# Conn_B.net
KiCad netlist of a schematic drawn in Altium Designer
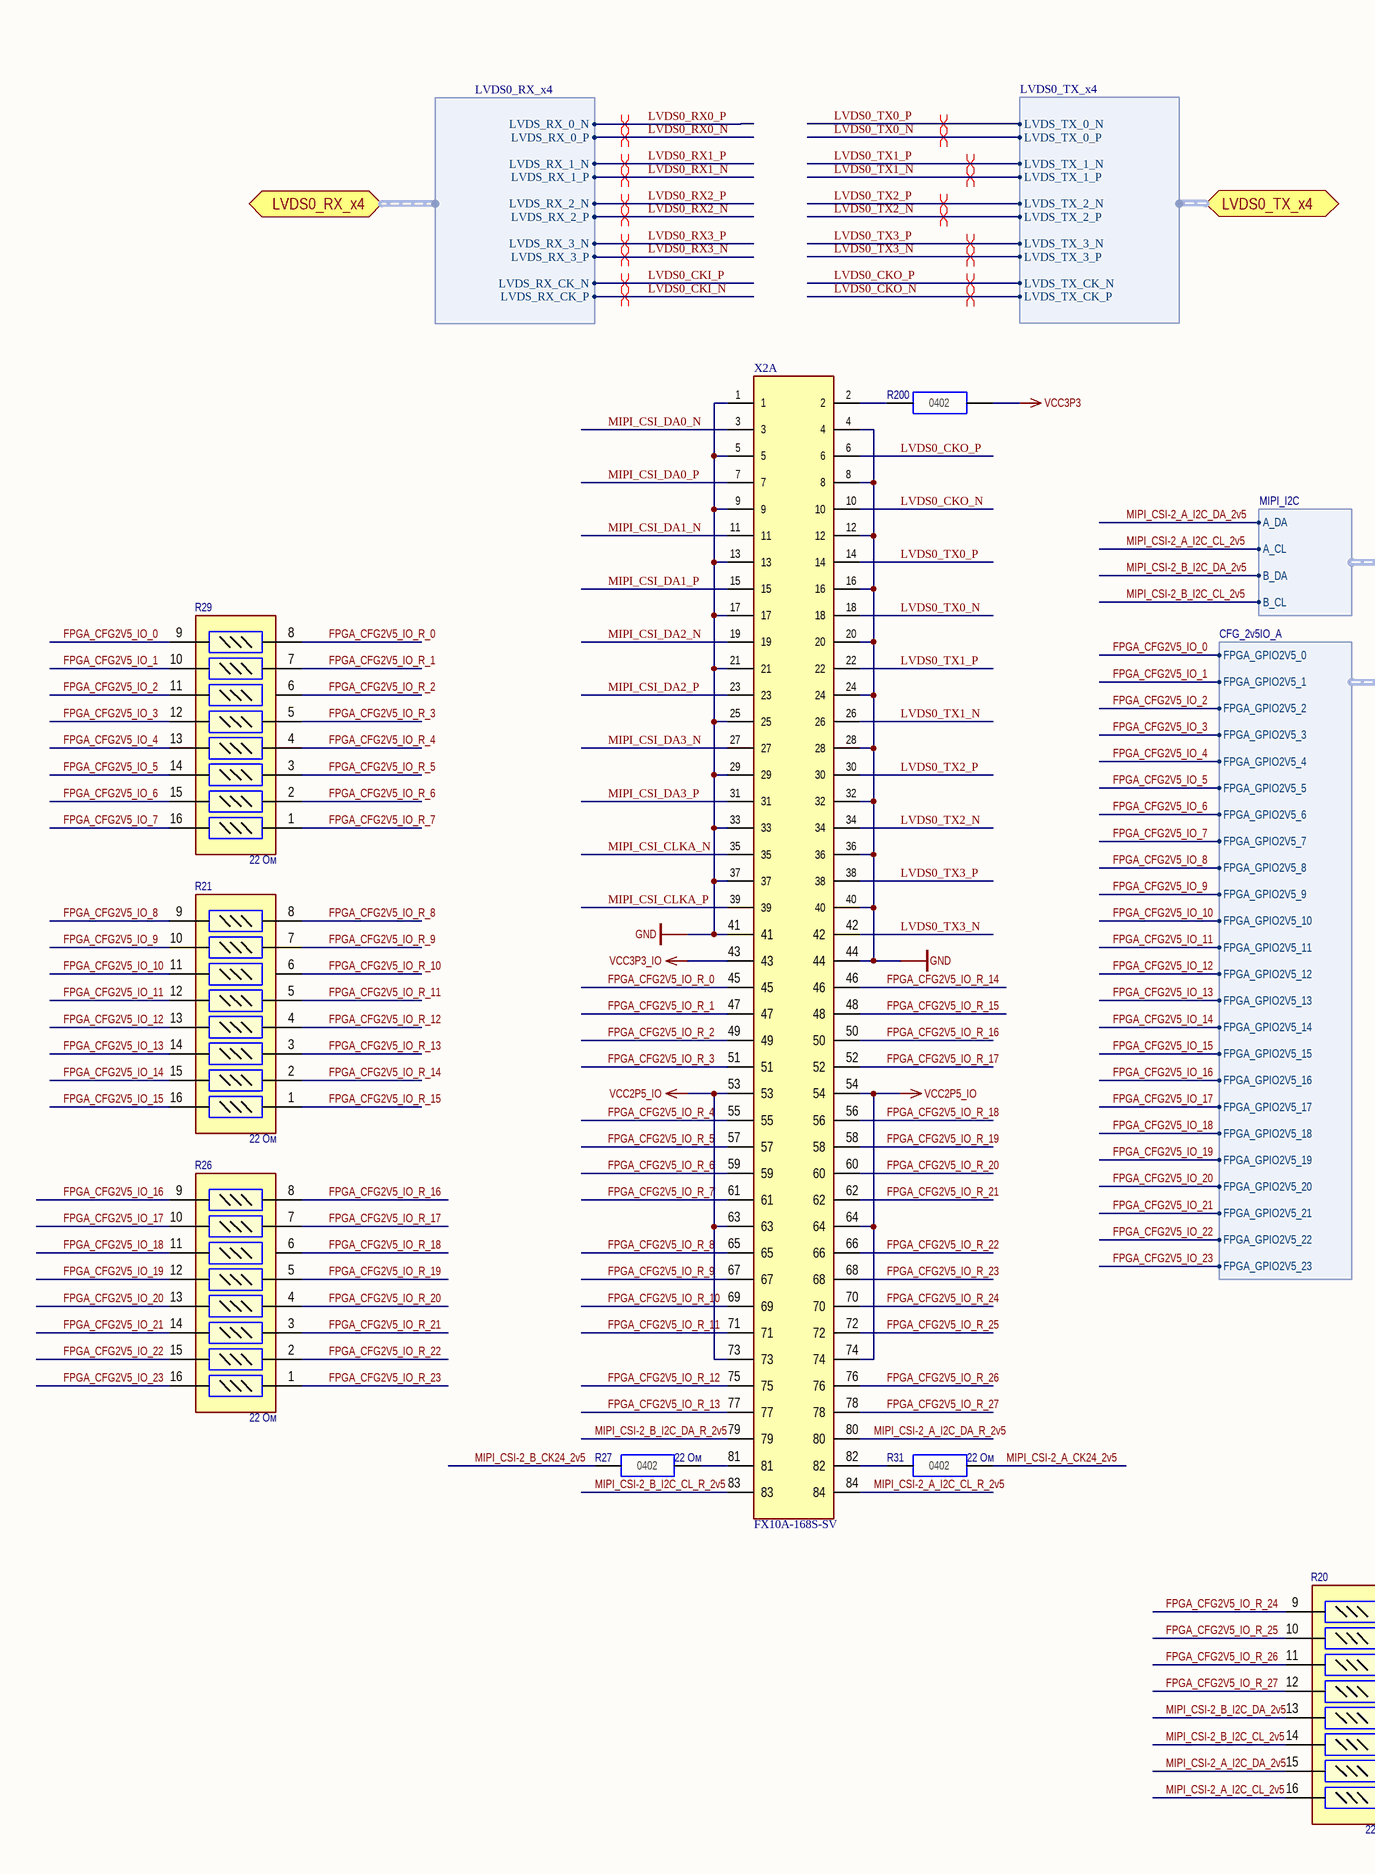
[diagram p0: Conn_B.SchDoc, left]
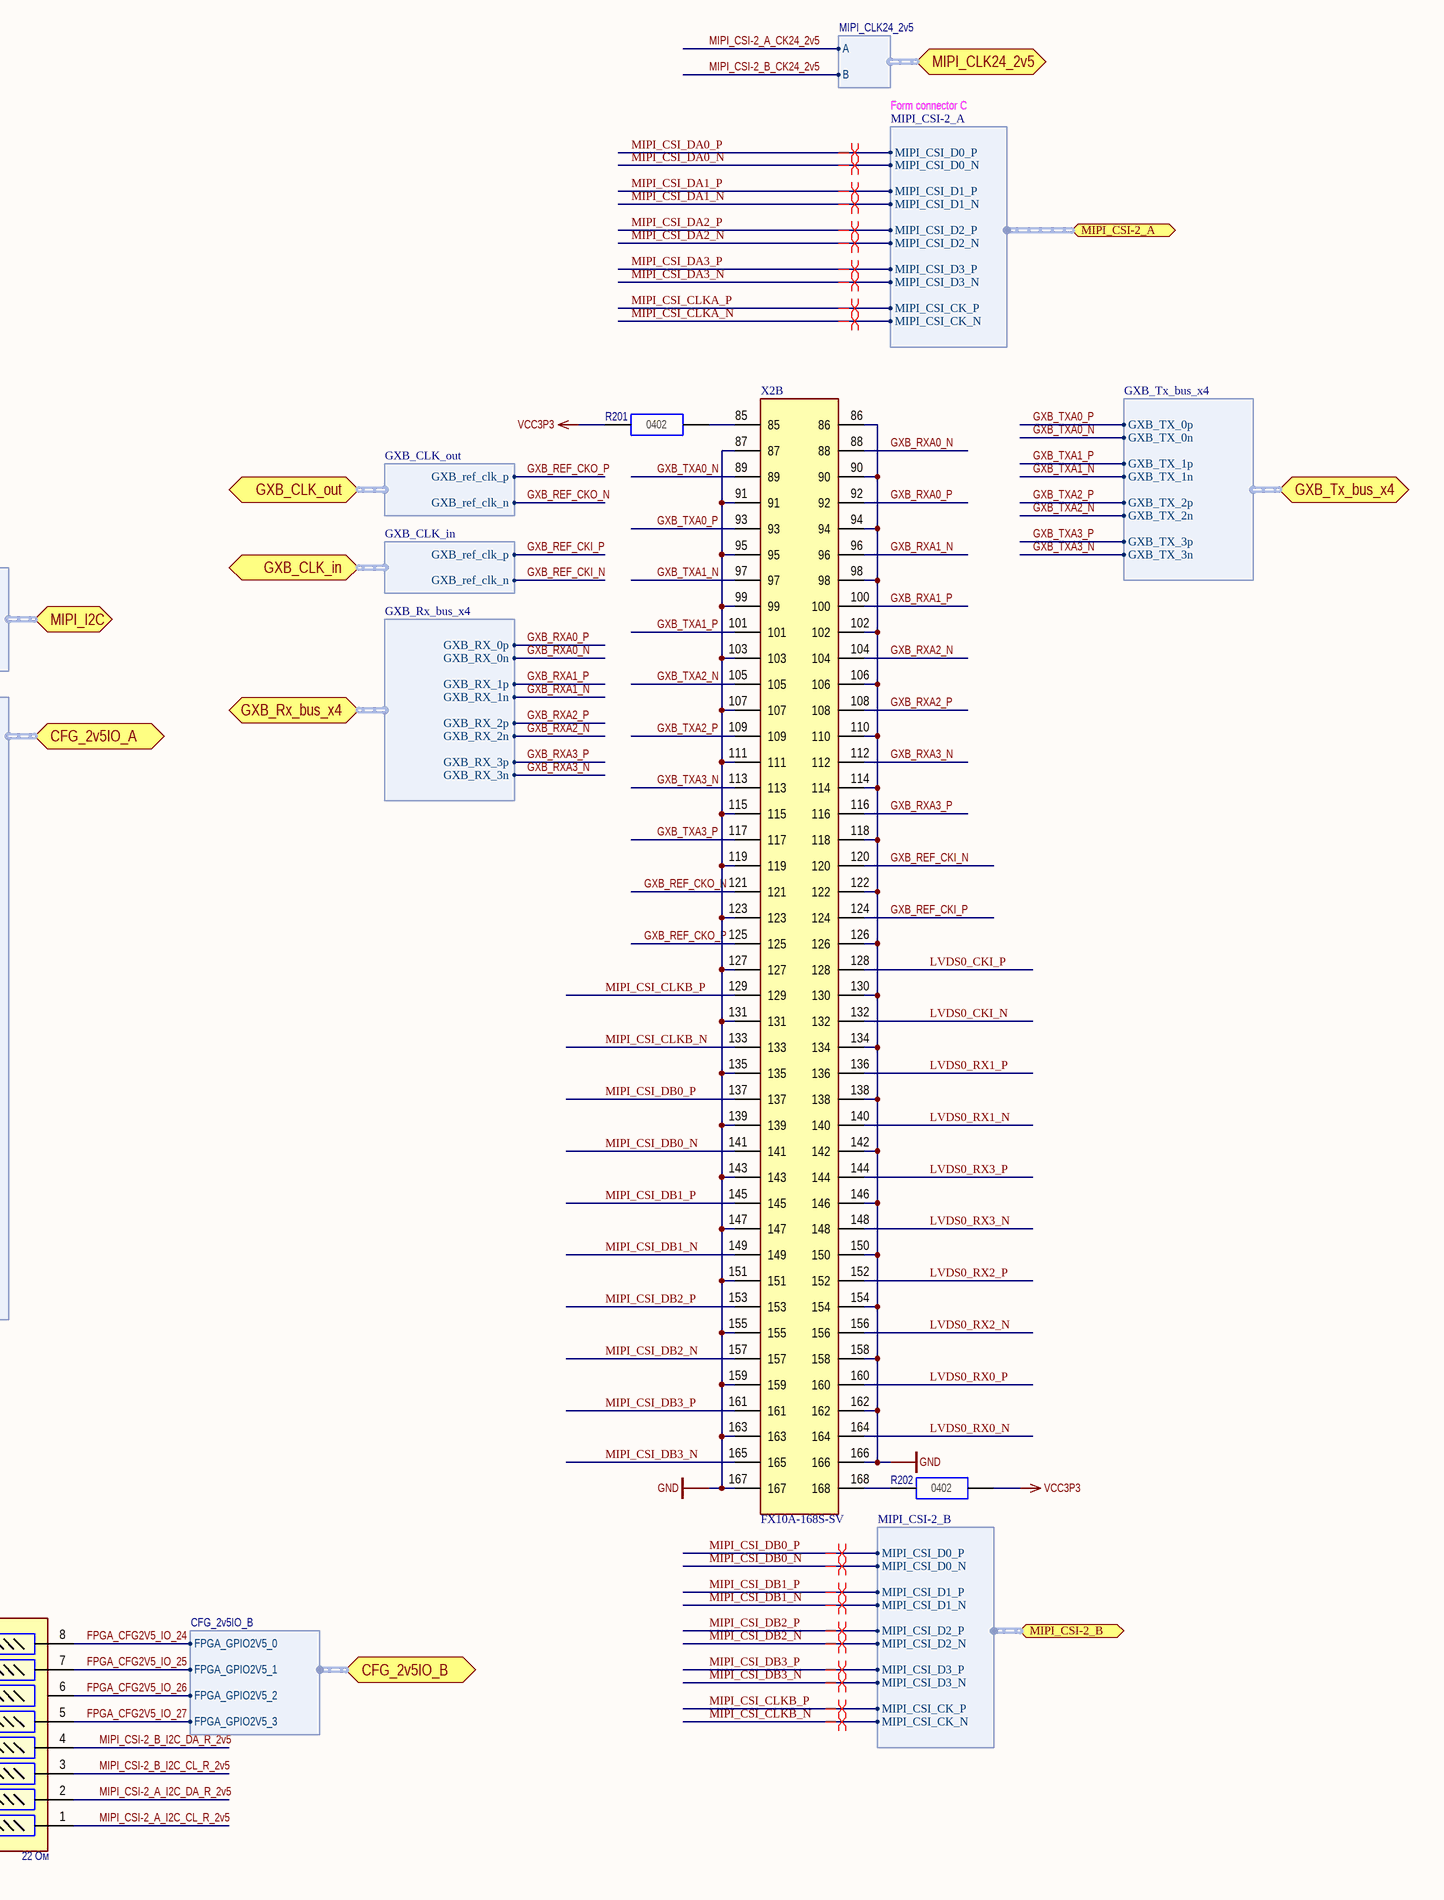
[diagram p1: Conn_B.SchDoc, right]

(export (version "E")
  (design (tool "Eeschema 10.0.6"))
  (components
    (comp (ref "R20")
      (value "22 Ом")
      (footprint "YC248")
      (description "Набор чип резисторов")
      (fields (field (name "Comment") "YC248-JR-07-22 Ом"))
      (libsource (lib "SD_IC") (part "YC248-JR-07-#"))
    )
    (comp (ref "R21")
      (value "22 Ом")
      (footprint "YC248")
      (description "Набор чип резисторов")
      (fields (field (name "Comment") "YC248-JR-07-22 Ом"))
      (libsource (lib "SD_IC") (part "YC248-JR-07-#"))
    )
    (comp (ref "R26")
      (value "22 Ом")
      (footprint "YC248")
      (description "Набор чип резисторов")
      (fields (field (name "Comment") "YC248-JR-07-22 Ом"))
      (libsource (lib "SD_IC") (part "YC248-JR-07-#"))
    )
    (comp (ref "R27")
      (value "22 Ом")
      (footprint "CR0402(1005)")
      (description "Чип резистор")
      (fields (field (name "TOLERANCE") "5%") (field (name "Comment") "CR0402-22 Ом-±5%"))
      (libsource (lib "Чип резисторы") (part "CR0402-#-±5%"))
    )
    (comp (ref "R29")
      (value "22 Ом")
      (footprint "YC248")
      (description "Набор чип резисторов")
      (fields (field (name "Comment") "YC248-JR-07-22 Ом"))
      (libsource (lib "SD_IC") (part "YC248-JR-07-#"))
    )
    (comp (ref "R31")
      (value "22 Ом")
      (footprint "CR0402(1005)")
      (description "Чип резистор")
      (fields (field (name "TOLERANCE") "5%") (field (name "Comment") "CR0402-22 Ом-±5%"))
      (libsource (lib "Чип резисторы") (part "CR0402-#-±5%"))
    )
    (comp (ref "R200")
      (value "CR0402-0 Ом-±5%")
      (footprint "CR0402(1005)")
      (description "Чип резистор")
      (fields (field (name "TOLERANCE") "5%"))
      (libsource (lib "Резисторы") (part "CR0402-#-±5%"))
    )
    (comp (ref "R201")
      (value "CR0402-0 Ом-±5%")
      (footprint "CR0402(1005)")
      (description "Чип резистор")
      (fields (field (name "TOLERANCE") "5%"))
      (libsource (lib "Резисторы") (part "CR0402-#-±5%"))
    )
    (comp (ref "R202")
      (value "CR0402-0 Ом-±5%")
      (footprint "CR0402(1005)")
      (description "Чип резистор")
      (fields (field (name "TOLERANCE") "5%"))
      (libsource (lib "Резисторы") (part "CR0402-#-±5%"))
    )
    (comp (ref "X2")
      (value "FX10A-168S-SV")
      (footprint "FX10A-168S-SV")
      (libsource (lib "SD_IC") (part "FX10A-168S-SV"))
    )
  )
  (nets
    (net (code "13") (name "/FPGA_CFG2V5_IO_0") (class "Default")
      (node (ref "R29") (pin "9") (pintype "passive"))
    )
    (net (code "14") (name "/FPGA_CFG2V5_IO_1") (class "Default")
      (node (ref "R29") (pin "10") (pintype "passive"))
    )
    (net (code "15") (name "/FPGA_CFG2V5_IO_2") (class "Default")
      (node (ref "R29") (pin "11") (pintype "passive"))
    )
    (net (code "16") (name "/FPGA_CFG2V5_IO_3") (class "Default")
      (node (ref "R29") (pin "12") (pintype "passive"))
    )
    (net (code "17") (name "/FPGA_CFG2V5_IO_4") (class "Default")
      (node (ref "R29") (pin "13") (pintype "passive"))
    )
    (net (code "18") (name "/FPGA_CFG2V5_IO_5") (class "Default")
      (node (ref "R29") (pin "14") (pintype "passive"))
    )
    (net (code "19") (name "/FPGA_CFG2V5_IO_6") (class "Default")
      (node (ref "R29") (pin "15") (pintype "passive"))
    )
    (net (code "20") (name "/FPGA_CFG2V5_IO_7") (class "Default")
      (node (ref "R29") (pin "16") (pintype "passive"))
    )
    (net (code "21") (name "/FPGA_CFG2V5_IO_8") (class "Default")
      (node (ref "R21") (pin "9") (pintype "passive"))
    )
    (net (code "22") (name "/FPGA_CFG2V5_IO_9") (class "Default")
      (node (ref "R21") (pin "10") (pintype "passive"))
    )
    (net (code "23") (name "/FPGA_CFG2V5_IO_10") (class "Default")
      (node (ref "R21") (pin "11") (pintype "passive"))
    )
    (net (code "24") (name "/FPGA_CFG2V5_IO_11") (class "Default")
      (node (ref "R21") (pin "12") (pintype "passive"))
    )
    (net (code "25") (name "/FPGA_CFG2V5_IO_12") (class "Default")
      (node (ref "R21") (pin "13") (pintype "passive"))
    )
    (net (code "26") (name "/FPGA_CFG2V5_IO_13") (class "Default")
      (node (ref "R21") (pin "14") (pintype "passive"))
    )
    (net (code "27") (name "/FPGA_CFG2V5_IO_14") (class "Default")
      (node (ref "R21") (pin "15") (pintype "passive"))
    )
    (net (code "28") (name "/FPGA_CFG2V5_IO_15") (class "Default")
      (node (ref "R21") (pin "16") (pintype "passive"))
    )
    (net (code "29") (name "/FPGA_CFG2V5_IO_16") (class "Default")
      (node (ref "R26") (pin "9") (pintype "passive"))
    )
    (net (code "30") (name "/FPGA_CFG2V5_IO_17") (class "Default")
      (node (ref "R26") (pin "10") (pintype "passive"))
    )
    (net (code "31") (name "/FPGA_CFG2V5_IO_18") (class "Default")
      (node (ref "R26") (pin "11") (pintype "passive"))
    )
    (net (code "32") (name "/FPGA_CFG2V5_IO_19") (class "Default")
      (node (ref "R26") (pin "12") (pintype "passive"))
    )
    (net (code "33") (name "/FPGA_CFG2V5_IO_20") (class "Default")
      (node (ref "R26") (pin "13") (pintype "passive"))
    )
    (net (code "34") (name "/FPGA_CFG2V5_IO_21") (class "Default")
      (node (ref "R26") (pin "14") (pintype "passive"))
    )
    (net (code "35") (name "/FPGA_CFG2V5_IO_22") (class "Default")
      (node (ref "R26") (pin "15") (pintype "passive"))
    )
    (net (code "36") (name "/FPGA_CFG2V5_IO_23") (class "Default")
      (node (ref "R26") (pin "16") (pintype "passive"))
    )
    (net (code "37") (name "/FPGA_CFG2V5_IO_24") (class "Default")
      (node (ref "R20") (pin "8") (pintype "passive"))
    )
    (net (code "38") (name "/FPGA_CFG2V5_IO_25") (class "Default")
      (node (ref "R20") (pin "7") (pintype "passive"))
    )
    (net (code "39") (name "/FPGA_CFG2V5_IO_26") (class "Default")
      (node (ref "R20") (pin "6") (pintype "passive"))
    )
    (net (code "40") (name "/FPGA_CFG2V5_IO_27") (class "Default")
      (node (ref "R20") (pin "5") (pintype "passive"))
    )
    (net (code "41") (name "/FPGA_CFG2V5_IO_R_0") (class "Default")
      (node (ref "R29") (pin "8") (pintype "passive"))
      (node (ref "X2") (pin "45") (pinfunction "45_45") (pintype "passive"))
    )
    (net (code "42") (name "/FPGA_CFG2V5_IO_R_1") (class "Default")
      (node (ref "R29") (pin "7") (pintype "passive"))
      (node (ref "X2") (pin "47") (pinfunction "47_47") (pintype "passive"))
    )
    (net (code "43") (name "/FPGA_CFG2V5_IO_R_2") (class "Default")
      (node (ref "R29") (pin "6") (pintype "passive"))
      (node (ref "X2") (pin "49") (pinfunction "49_49") (pintype "passive"))
    )
    (net (code "44") (name "/FPGA_CFG2V5_IO_R_3") (class "Default")
      (node (ref "R29") (pin "5") (pintype "passive"))
      (node (ref "X2") (pin "51") (pinfunction "51_51") (pintype "passive"))
    )
    (net (code "45") (name "/FPGA_CFG2V5_IO_R_4") (class "Default")
      (node (ref "R29") (pin "4") (pintype "passive"))
      (node (ref "X2") (pin "55") (pinfunction "55_55") (pintype "passive"))
    )
    (net (code "46") (name "/FPGA_CFG2V5_IO_R_5") (class "Default")
      (node (ref "R29") (pin "3") (pintype "passive"))
      (node (ref "X2") (pin "57") (pinfunction "57_57") (pintype "passive"))
    )
    (net (code "47") (name "/FPGA_CFG2V5_IO_R_6") (class "Default")
      (node (ref "R29") (pin "2") (pintype "passive"))
      (node (ref "X2") (pin "59") (pinfunction "59_59") (pintype "passive"))
    )
    (net (code "48") (name "/FPGA_CFG2V5_IO_R_7") (class "Default")
      (node (ref "R29") (pin "1") (pintype "passive"))
      (node (ref "X2") (pin "61") (pinfunction "61_61") (pintype "passive"))
    )
    (net (code "49") (name "/FPGA_CFG2V5_IO_R_8") (class "Default")
      (node (ref "R21") (pin "8") (pintype "passive"))
      (node (ref "X2") (pin "65") (pinfunction "65_65") (pintype "passive"))
    )
    (net (code "50") (name "/FPGA_CFG2V5_IO_R_9") (class "Default")
      (node (ref "R21") (pin "7") (pintype "passive"))
      (node (ref "X2") (pin "67") (pinfunction "67_67") (pintype "passive"))
    )
    (net (code "51") (name "/FPGA_CFG2V5_IO_R_10") (class "Default")
      (node (ref "R21") (pin "6") (pintype "passive"))
      (node (ref "X2") (pin "69") (pinfunction "69_69") (pintype "passive"))
    )
    (net (code "52") (name "/FPGA_CFG2V5_IO_R_11") (class "Default")
      (node (ref "R21") (pin "5") (pintype "passive"))
      (node (ref "X2") (pin "71") (pinfunction "71_71") (pintype "passive"))
    )
    (net (code "53") (name "/FPGA_CFG2V5_IO_R_12") (class "Default")
      (node (ref "R21") (pin "4") (pintype "passive"))
      (node (ref "X2") (pin "75") (pinfunction "75_75") (pintype "passive"))
    )
    (net (code "54") (name "/FPGA_CFG2V5_IO_R_13") (class "Default")
      (node (ref "R21") (pin "3") (pintype "passive"))
      (node (ref "X2") (pin "77") (pinfunction "77_77") (pintype "passive"))
    )
    (net (code "55") (name "/FPGA_CFG2V5_IO_R_14") (class "Default")
      (node (ref "R21") (pin "2") (pintype "passive"))
      (node (ref "X2") (pin "46") (pinfunction "46_46") (pintype "passive"))
    )
    (net (code "56") (name "/FPGA_CFG2V5_IO_R_15") (class "Default")
      (node (ref "R21") (pin "1") (pintype "passive"))
      (node (ref "X2") (pin "48") (pinfunction "48_48") (pintype "passive"))
    )
    (net (code "57") (name "/FPGA_CFG2V5_IO_R_16") (class "Default")
      (node (ref "R26") (pin "8") (pintype "passive"))
      (node (ref "X2") (pin "50") (pinfunction "50_50") (pintype "passive"))
    )
    (net (code "58") (name "/FPGA_CFG2V5_IO_R_17") (class "Default")
      (node (ref "R26") (pin "7") (pintype "passive"))
      (node (ref "X2") (pin "52") (pinfunction "52_52") (pintype "passive"))
    )
    (net (code "59") (name "/FPGA_CFG2V5_IO_R_18") (class "Default")
      (node (ref "R26") (pin "6") (pintype "passive"))
      (node (ref "X2") (pin "56") (pinfunction "56_56") (pintype "passive"))
    )
    (net (code "60") (name "/FPGA_CFG2V5_IO_R_19") (class "Default")
      (node (ref "R26") (pin "5") (pintype "passive"))
      (node (ref "X2") (pin "58") (pinfunction "58_58") (pintype "passive"))
    )
    (net (code "61") (name "/FPGA_CFG2V5_IO_R_20") (class "Default")
      (node (ref "R26") (pin "4") (pintype "passive"))
      (node (ref "X2") (pin "60") (pinfunction "60_60") (pintype "passive"))
    )
    (net (code "62") (name "/FPGA_CFG2V5_IO_R_21") (class "Default")
      (node (ref "R26") (pin "3") (pintype "passive"))
      (node (ref "X2") (pin "62") (pinfunction "62_62") (pintype "passive"))
    )
    (net (code "63") (name "/FPGA_CFG2V5_IO_R_22") (class "Default")
      (node (ref "R26") (pin "2") (pintype "passive"))
      (node (ref "X2") (pin "66") (pinfunction "66_66") (pintype "passive"))
    )
    (net (code "64") (name "/FPGA_CFG2V5_IO_R_23") (class "Default")
      (node (ref "R26") (pin "1") (pintype "passive"))
      (node (ref "X2") (pin "68") (pinfunction "68_68") (pintype "passive"))
    )
    (net (code "65") (name "/FPGA_CFG2V5_IO_R_24") (class "Default")
      (node (ref "R20") (pin "9") (pintype "passive"))
      (node (ref "X2") (pin "70") (pinfunction "70_70") (pintype "passive"))
    )
    (net (code "66") (name "/FPGA_CFG2V5_IO_R_25") (class "Default")
      (node (ref "R20") (pin "10") (pintype "passive"))
      (node (ref "X2") (pin "72") (pinfunction "72_72") (pintype "passive"))
    )
    (net (code "67") (name "/FPGA_CFG2V5_IO_R_26") (class "Default")
      (node (ref "R20") (pin "11") (pintype "passive"))
      (node (ref "X2") (pin "76") (pinfunction "76_76") (pintype "passive"))
    )
    (net (code "68") (name "/FPGA_CFG2V5_IO_R_27") (class "Default")
      (node (ref "R20") (pin "12") (pintype "passive"))
      (node (ref "X2") (pin "78") (pinfunction "78_78") (pintype "passive"))
    )
    (net (code "69") (name "/GXB_REF_CKI_N") (class "Default")
      (node (ref "X2") (pin "120") (pinfunction "120_120") (pintype "passive"))
    )
    (net (code "70") (name "/GXB_REF_CKI_P") (class "Default")
      (node (ref "X2") (pin "124") (pinfunction "124_124") (pintype "passive"))
    )
    (net (code "71") (name "/GXB_REF_CKO_N") (class "Default")
      (node (ref "X2") (pin "121") (pinfunction "121_121") (pintype "passive"))
    )
    (net (code "72") (name "/GXB_REF_CKO_P") (class "Default")
      (node (ref "X2") (pin "125") (pinfunction "125_125") (pintype "passive"))
    )
    (net (code "73") (name "/GXB_RXA0_N") (class "Default")
      (node (ref "X2") (pin "88") (pinfunction "88_88") (pintype "passive"))
    )
    (net (code "74") (name "/GXB_RXA0_P") (class "Default")
      (node (ref "X2") (pin "92") (pinfunction "92_92") (pintype "passive"))
    )
    (net (code "75") (name "/GXB_RXA1_N") (class "Default")
      (node (ref "X2") (pin "96") (pinfunction "96_96") (pintype "passive"))
    )
    (net (code "76") (name "/GXB_RXA1_P") (class "Default")
      (node (ref "X2") (pin "100") (pinfunction "100_100") (pintype "passive"))
    )
    (net (code "77") (name "/GXB_RXA2_N") (class "Default")
      (node (ref "X2") (pin "104") (pinfunction "104_104") (pintype "passive"))
    )
    (net (code "78") (name "/GXB_RXA2_P") (class "Default")
      (node (ref "X2") (pin "108") (pinfunction "108_108") (pintype "passive"))
    )
    (net (code "79") (name "/GXB_RXA3_N") (class "Default")
      (node (ref "X2") (pin "112") (pinfunction "112_112") (pintype "passive"))
    )
    (net (code "80") (name "/GXB_RXA3_P") (class "Default")
      (node (ref "X2") (pin "116") (pinfunction "116_116") (pintype "passive"))
    )
    (net (code "81") (name "/GXB_TXA0_N") (class "Default")
      (node (ref "X2") (pin "89") (pinfunction "89_89") (pintype "passive"))
    )
    (net (code "82") (name "/GXB_TXA0_P") (class "Default")
      (node (ref "X2") (pin "93") (pinfunction "93_93") (pintype "passive"))
    )
    (net (code "83") (name "/GXB_TXA1_N") (class "Default")
      (node (ref "X2") (pin "97") (pinfunction "97_97") (pintype "passive"))
    )
    (net (code "84") (name "/GXB_TXA1_P") (class "Default")
      (node (ref "X2") (pin "101") (pinfunction "101_101") (pintype "passive"))
    )
    (net (code "85") (name "/GXB_TXA2_N") (class "Default")
      (node (ref "X2") (pin "105") (pinfunction "105_105") (pintype "passive"))
    )
    (net (code "86") (name "/GXB_TXA2_P") (class "Default")
      (node (ref "X2") (pin "109") (pinfunction "109_109") (pintype "passive"))
    )
    (net (code "87") (name "/GXB_TXA3_N") (class "Default")
      (node (ref "X2") (pin "113") (pinfunction "113_113") (pintype "passive"))
    )
    (net (code "88") (name "/GXB_TXA3_P") (class "Default")
      (node (ref "X2") (pin "117") (pinfunction "117_117") (pintype "passive"))
    )
    (net (code "89") (name "/LVDS0_CKI_N") (class "Default")
      (node (ref "X2") (pin "132") (pinfunction "132_132") (pintype "passive"))
    )
    (net (code "90") (name "/LVDS0_CKI_P") (class "Default")
      (node (ref "X2") (pin "128") (pinfunction "128_128") (pintype "passive"))
    )
    (net (code "91") (name "/LVDS0_CKO_N") (class "Default")
      (node (ref "X2") (pin "10") (pinfunction "10_10") (pintype "passive"))
    )
    (net (code "92") (name "/LVDS0_CKO_P") (class "Default")
      (node (ref "X2") (pin "6") (pinfunction "6_6") (pintype "passive"))
    )
    (net (code "93") (name "/LVDS0_RX0_N") (class "Default")
      (node (ref "X2") (pin "164") (pinfunction "164_164") (pintype "passive"))
    )
    (net (code "94") (name "/LVDS0_RX0_P") (class "Default")
      (node (ref "X2") (pin "160") (pinfunction "160_160") (pintype "passive"))
    )
    (net (code "95") (name "/LVDS0_RX1_N") (class "Default")
      (node (ref "X2") (pin "140") (pinfunction "140_140") (pintype "passive"))
    )
    (net (code "96") (name "/LVDS0_RX1_P") (class "Default")
      (node (ref "X2") (pin "136") (pinfunction "136_136") (pintype "passive"))
    )
    (net (code "97") (name "/LVDS0_RX2_N") (class "Default")
      (node (ref "X2") (pin "156") (pinfunction "156_156") (pintype "passive"))
    )
    (net (code "98") (name "/LVDS0_RX2_P") (class "Default")
      (node (ref "X2") (pin "152") (pinfunction "152_152") (pintype "passive"))
    )
    (net (code "99") (name "/LVDS0_RX3_N") (class "Default")
      (node (ref "X2") (pin "148") (pinfunction "148_148") (pintype "passive"))
    )
    (net (code "100") (name "/LVDS0_RX3_P") (class "Default")
      (node (ref "X2") (pin "144") (pinfunction "144_144") (pintype "passive"))
    )
    (net (code "101") (name "/LVDS0_TX0_N") (class "Default")
      (node (ref "X2") (pin "18") (pinfunction "18_18") (pintype "passive"))
    )
    (net (code "102") (name "/LVDS0_TX0_P") (class "Default")
      (node (ref "X2") (pin "14") (pinfunction "14_14") (pintype "passive"))
    )
    (net (code "103") (name "/LVDS0_TX1_N") (class "Default")
      (node (ref "X2") (pin "26") (pinfunction "26_26") (pintype "passive"))
    )
    (net (code "104") (name "/LVDS0_TX1_P") (class "Default")
      (node (ref "X2") (pin "22") (pinfunction "22_22") (pintype "passive"))
    )
    (net (code "105") (name "/LVDS0_TX2_N") (class "Default")
      (node (ref "X2") (pin "34") (pinfunction "34_34") (pintype "passive"))
    )
    (net (code "106") (name "/LVDS0_TX2_P") (class "Default")
      (node (ref "X2") (pin "30") (pinfunction "30_30") (pintype "passive"))
    )
    (net (code "107") (name "/LVDS0_TX3_N") (class "Default")
      (node (ref "X2") (pin "42") (pinfunction "42_42") (pintype "passive"))
    )
    (net (code "108") (name "/LVDS0_TX3_P") (class "Default")
      (node (ref "X2") (pin "38") (pinfunction "38_38") (pintype "passive"))
    )
    (net (code "109") (name "/MIPI_CSI-2_A_CK24_2v5") (class "Default")
      (node (ref "R31") (pin "2") (pinfunction "-_2") (pintype "passive"))
    )
    (net (code "110") (name "/MIPI_CSI-2_A_I2C_CL_2v5") (class "Default")
      (node (ref "R20") (pin "16") (pintype "passive"))
    )
    (net (code "111") (name "/MIPI_CSI-2_A_I2C_CL_R_2v5") (class "Default")
      (node (ref "R20") (pin "1") (pintype "passive"))
      (node (ref "X2") (pin "84") (pinfunction "84_84") (pintype "passive"))
    )
    (net (code "112") (name "/MIPI_CSI-2_A_I2C_DA_2v5") (class "Default")
      (node (ref "R20") (pin "15") (pintype "passive"))
    )
    (net (code "113") (name "/MIPI_CSI-2_A_I2C_DA_R_2v5") (class "Default")
      (node (ref "R20") (pin "2") (pintype "passive"))
      (node (ref "X2") (pin "80") (pinfunction "80_80") (pintype "passive"))
    )
    (net (code "114") (name "/MIPI_CSI-2_B_CK24_2v5") (class "Default")
      (node (ref "R27") (pin "1") (pinfunction "+_1") (pintype "passive"))
    )
    (net (code "115") (name "/MIPI_CSI-2_B_I2C_CL_2v5") (class "Default")
      (node (ref "R20") (pin "14") (pintype "passive"))
    )
    (net (code "116") (name "/MIPI_CSI-2_B_I2C_CL_R_2v5") (class "Default")
      (node (ref "R20") (pin "3") (pintype "passive"))
      (node (ref "X2") (pin "83") (pinfunction "83_83") (pintype "passive"))
    )
    (net (code "117") (name "/MIPI_CSI-2_B_I2C_DA_2v5") (class "Default")
      (node (ref "R20") (pin "13") (pintype "passive"))
    )
    (net (code "118") (name "/MIPI_CSI-2_B_I2C_DA_R_2v5") (class "Default")
      (node (ref "R20") (pin "4") (pintype "passive"))
      (node (ref "X2") (pin "79") (pinfunction "79_79") (pintype "passive"))
    )
    (net (code "119") (name "/MIPI_CSI_CLKA_N") (class "Default")
      (node (ref "X2") (pin "35") (pinfunction "35_35") (pintype "passive"))
    )
    (net (code "120") (name "/MIPI_CSI_CLKA_P") (class "Default")
      (node (ref "X2") (pin "39") (pinfunction "39_39") (pintype "passive"))
    )
    (net (code "121") (name "/MIPI_CSI_CLKB_N") (class "Default")
      (node (ref "X2") (pin "133") (pinfunction "133_133") (pintype "passive"))
    )
    (net (code "122") (name "/MIPI_CSI_CLKB_P") (class "Default")
      (node (ref "X2") (pin "129") (pinfunction "129_129") (pintype "passive"))
    )
    (net (code "123") (name "/MIPI_CSI_DA0_N") (class "Default")
      (node (ref "X2") (pin "3") (pinfunction "3_3") (pintype "passive"))
    )
    (net (code "124") (name "/MIPI_CSI_DA0_P") (class "Default")
      (node (ref "X2") (pin "7") (pinfunction "7_7") (pintype "passive"))
    )
    (net (code "125") (name "/MIPI_CSI_DA1_N") (class "Default")
      (node (ref "X2") (pin "11") (pinfunction "11_11") (pintype "passive"))
    )
    (net (code "126") (name "/MIPI_CSI_DA1_P") (class "Default")
      (node (ref "X2") (pin "15") (pinfunction "15_15") (pintype "passive"))
    )
    (net (code "127") (name "/MIPI_CSI_DA2_N") (class "Default")
      (node (ref "X2") (pin "19") (pinfunction "19_19") (pintype "passive"))
    )
    (net (code "128") (name "/MIPI_CSI_DA2_P") (class "Default")
      (node (ref "X2") (pin "23") (pinfunction "23_23") (pintype "passive"))
    )
    (net (code "129") (name "/MIPI_CSI_DA3_N") (class "Default")
      (node (ref "X2") (pin "27") (pinfunction "27_27") (pintype "passive"))
    )
    (net (code "130") (name "/MIPI_CSI_DA3_P") (class "Default")
      (node (ref "X2") (pin "31") (pinfunction "31_31") (pintype "passive"))
    )
    (net (code "131") (name "/MIPI_CSI_DB0_N") (class "Default")
      (node (ref "X2") (pin "141") (pinfunction "141_141") (pintype "passive"))
    )
    (net (code "132") (name "/MIPI_CSI_DB0_P") (class "Default")
      (node (ref "X2") (pin "137") (pinfunction "137_137") (pintype "passive"))
    )
    (net (code "133") (name "/MIPI_CSI_DB1_N") (class "Default")
      (node (ref "X2") (pin "149") (pinfunction "149_149") (pintype "passive"))
    )
    (net (code "134") (name "/MIPI_CSI_DB1_P") (class "Default")
      (node (ref "X2") (pin "145") (pinfunction "145_145") (pintype "passive"))
    )
    (net (code "135") (name "/MIPI_CSI_DB2_N") (class "Default")
      (node (ref "X2") (pin "157") (pinfunction "157_157") (pintype "passive"))
    )
    (net (code "136") (name "/MIPI_CSI_DB2_P") (class "Default")
      (node (ref "X2") (pin "153") (pinfunction "153_153") (pintype "passive"))
    )
    (net (code "137") (name "/MIPI_CSI_DB3_N") (class "Default")
      (node (ref "X2") (pin "165") (pinfunction "165_165") (pintype "passive"))
    )
    (net (code "138") (name "/MIPI_CSI_DB3_P") (class "Default")
      (node (ref "X2") (pin "161") (pinfunction "161_161") (pintype "passive"))
    )
    (net (code "151") (name "GND") (class "Default")
      (node (ref "X2") (pin "1") (pinfunction "1_1") (pintype "passive"))
      (node (ref "X2") (pin "102") (pinfunction "102_102") (pintype "passive"))
      (node (ref "X2") (pin "103") (pinfunction "103_103") (pintype "passive"))
      (node (ref "X2") (pin "106") (pinfunction "106_106") (pintype "passive"))
      (node (ref "X2") (pin "107") (pinfunction "107_107") (pintype "passive"))
      (node (ref "X2") (pin "110") (pinfunction "110_110") (pintype "passive"))
      (node (ref "X2") (pin "111") (pinfunction "111_111") (pintype "passive"))
      (node (ref "X2") (pin "114") (pinfunction "114_114") (pintype "passive"))
      (node (ref "X2") (pin "115") (pinfunction "115_115") (pintype "passive"))
      (node (ref "X2") (pin "118") (pinfunction "118_118") (pintype "passive"))
      (node (ref "X2") (pin "119") (pinfunction "119_119") (pintype "passive"))
      (node (ref "X2") (pin "12") (pinfunction "12_12") (pintype "passive"))
      (node (ref "X2") (pin "122") (pinfunction "122_122") (pintype "passive"))
      (node (ref "X2") (pin "123") (pinfunction "123_123") (pintype "passive"))
      (node (ref "X2") (pin "126") (pinfunction "126_126") (pintype "passive"))
      (node (ref "X2") (pin "127") (pinfunction "127_127") (pintype "passive"))
      (node (ref "X2") (pin "13") (pinfunction "13_13") (pintype "passive"))
      (node (ref "X2") (pin "130") (pinfunction "130_130") (pintype "passive"))
      (node (ref "X2") (pin "131") (pinfunction "131_131") (pintype "passive"))
      (node (ref "X2") (pin "134") (pinfunction "134_134") (pintype "passive"))
      (node (ref "X2") (pin "135") (pinfunction "135_135") (pintype "passive"))
      (node (ref "X2") (pin "138") (pinfunction "138_138") (pintype "passive"))
      (node (ref "X2") (pin "139") (pinfunction "139_139") (pintype "passive"))
      (node (ref "X2") (pin "142") (pinfunction "142_142") (pintype "passive"))
      (node (ref "X2") (pin "143") (pinfunction "143_143") (pintype "passive"))
      (node (ref "X2") (pin "146") (pinfunction "146_146") (pintype "passive"))
      (node (ref "X2") (pin "147") (pinfunction "147_147") (pintype "passive"))
      (node (ref "X2") (pin "150") (pinfunction "150_150") (pintype "passive"))
      (node (ref "X2") (pin "151") (pinfunction "151_151") (pintype "passive"))
      (node (ref "X2") (pin "154") (pinfunction "154_154") (pintype "passive"))
      (node (ref "X2") (pin "155") (pinfunction "155_155") (pintype "passive"))
      (node (ref "X2") (pin "158") (pinfunction "158_158") (pintype "passive"))
      (node (ref "X2") (pin "159") (pinfunction "159_159") (pintype "passive"))
      (node (ref "X2") (pin "16") (pinfunction "16_16") (pintype "passive"))
      (node (ref "X2") (pin "162") (pinfunction "162_162") (pintype "passive"))
      (node (ref "X2") (pin "163") (pinfunction "163_163") (pintype "passive"))
      (node (ref "X2") (pin "166") (pinfunction "166_166") (pintype "passive"))
      (node (ref "X2") (pin "167") (pinfunction "167_167") (pintype "passive"))
      (node (ref "X2") (pin "17") (pinfunction "17_17") (pintype "passive"))
      (node (ref "X2") (pin "20") (pinfunction "20_20") (pintype "passive"))
      (node (ref "X2") (pin "21") (pinfunction "21_21") (pintype "passive"))
      (node (ref "X2") (pin "24") (pinfunction "24_24") (pintype "passive"))
      (node (ref "X2") (pin "25") (pinfunction "25_25") (pintype "passive"))
      (node (ref "X2") (pin "28") (pinfunction "28_28") (pintype "passive"))
      (node (ref "X2") (pin "29") (pinfunction "29_29") (pintype "passive"))
      (node (ref "X2") (pin "32") (pinfunction "32_32") (pintype "passive"))
      (node (ref "X2") (pin "33") (pinfunction "33_33") (pintype "passive"))
      (node (ref "X2") (pin "36") (pinfunction "36_36") (pintype "passive"))
      (node (ref "X2") (pin "37") (pinfunction "37_37") (pintype "passive"))
      (node (ref "X2") (pin "4") (pinfunction "4_4") (pintype "passive"))
      (node (ref "X2") (pin "40") (pinfunction "40_40") (pintype "passive"))
      (node (ref "X2") (pin "41") (pinfunction "41_41") (pintype "passive"))
      (node (ref "X2") (pin "44") (pinfunction "44_44") (pintype "passive"))
      (node (ref "X2") (pin "5") (pinfunction "5_5") (pintype "passive"))
      (node (ref "X2") (pin "8") (pinfunction "8_8") (pintype "passive"))
      (node (ref "X2") (pin "86") (pinfunction "86_86") (pintype "passive"))
      (node (ref "X2") (pin "87") (pinfunction "87_87") (pintype "passive"))
      (node (ref "X2") (pin "9") (pinfunction "9_9") (pintype "passive"))
      (node (ref "X2") (pin "90") (pinfunction "90_90") (pintype "passive"))
      (node (ref "X2") (pin "91") (pinfunction "91_91") (pintype "passive"))
      (node (ref "X2") (pin "94") (pinfunction "94_94") (pintype "passive"))
      (node (ref "X2") (pin "95") (pinfunction "95_95") (pintype "passive"))
      (node (ref "X2") (pin "98") (pinfunction "98_98") (pintype "passive"))
      (node (ref "X2") (pin "99") (pinfunction "99_99") (pintype "passive"))
    )
    (net (code "152") (name "Net-(R27--)") (class "Default")
      (node (ref "R27") (pin "2") (pinfunction "-_2") (pintype "passive"))
      (node (ref "X2") (pin "81") (pinfunction "81_81") (pintype "passive"))
    )
    (net (code "153") (name "Net-(R31-+)") (class "Default")
      (node (ref "R31") (pin "1") (pinfunction "+_1") (pintype "passive"))
      (node (ref "X2") (pin "82") (pinfunction "82_82") (pintype "passive"))
    )
    (net (code "154") (name "Net-(R200-+)") (class "Default")
      (node (ref "R200") (pin "1") (pinfunction "+_1") (pintype "passive"))
      (node (ref "X2") (pin "2") (pinfunction "2_2") (pintype "passive"))
    )
    (net (code "155") (name "Net-(R201--)") (class "Default")
      (node (ref "R201") (pin "2") (pinfunction "-_2") (pintype "passive"))
      (node (ref "X2") (pin "85") (pinfunction "85_85") (pintype "passive"))
    )
    (net (code "156") (name "Net-(R202-+)") (class "Default")
      (node (ref "R202") (pin "1") (pinfunction "+_1") (pintype "passive"))
      (node (ref "X2") (pin "168") (pinfunction "168_168") (pintype "passive"))
    )
    (net (code "157") (name "VCC2P5_IO") (class "Default")
      (node (ref "X2") (pin "53") (pinfunction "53_53") (pintype "passive"))
      (node (ref "X2") (pin "54") (pinfunction "54_54") (pintype "passive"))
      (node (ref "X2") (pin "63") (pinfunction "63_63") (pintype "passive"))
      (node (ref "X2") (pin "64") (pinfunction "64_64") (pintype "passive"))
      (node (ref "X2") (pin "73") (pinfunction "73_73") (pintype "passive"))
      (node (ref "X2") (pin "74") (pinfunction "74_74") (pintype "passive"))
    )
    (net (code "158") (name "VCC3P3") (class "Default")
      (node (ref "R200") (pin "2") (pinfunction "-_2") (pintype "passive"))
      (node (ref "R201") (pin "1") (pinfunction "+_1") (pintype "passive"))
      (node (ref "R202") (pin "2") (pinfunction "-_2") (pintype "passive"))
    )
    (net (code "159") (name "VCC3P3_IO") (class "Default")
      (node (ref "X2") (pin "43") (pinfunction "43_43") (pintype "passive"))
    )
  )
)
